# display.net
KiCad netlist of a schematic drawn in Altium Designer
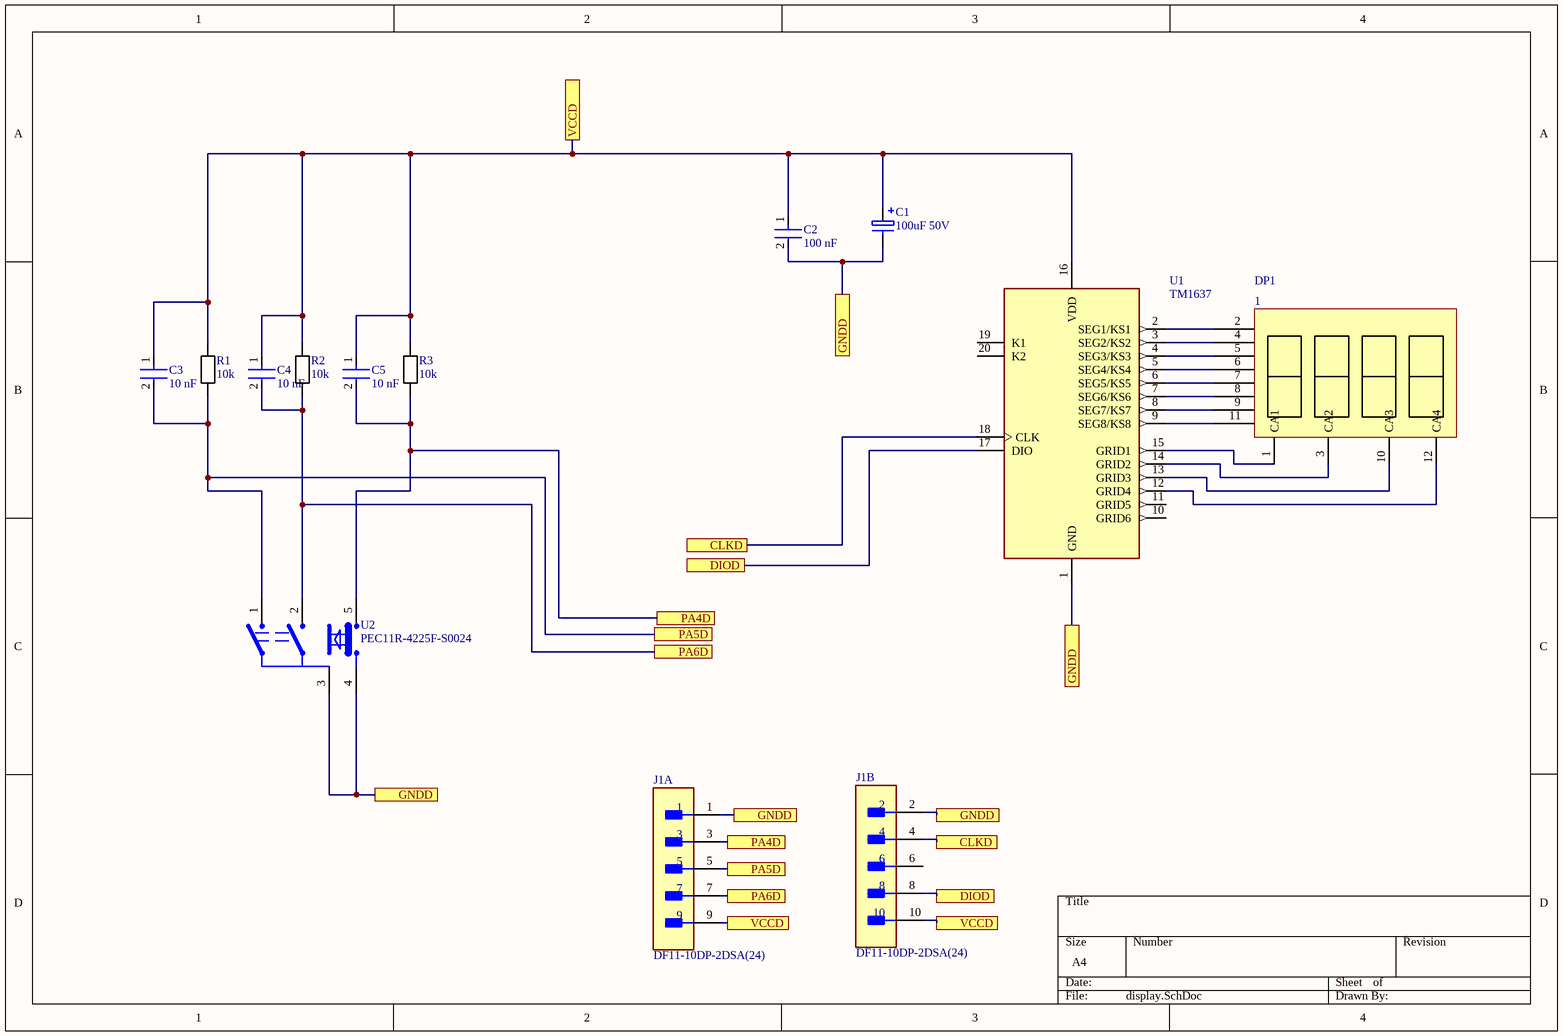
[diagram p0: display.SchDoc]

(export (version "E")
  (design (tool "Eeschema 10.0.6"))
  (components
    (comp (ref "1") (value "DP1") (footprint "7sigment") (libsource (lib "Schlib1") (part "7sigment")))
    (comp (ref "C1")
      (value "100uF 50V")
      (footprint "Elco 100uF 50V")
      (fields
        (field (name "PART NUMBER") "02015A270JAT2A")
        (field (name "MANUFACTURER") "AVX Interconnect / Elco")
      )
      (libsource (lib "Schlib1") (part "condensator 100uF 50V"))
    )
    (comp (ref "C2")
      (value "100 nF")
      (footprint "0805")
      (description "Chip Multilayer Ceramic Capacitors for General Purpose, 0805, 10uF, X5R, 15%, 10%, 25V")
      (fields (field (name "VOLTAGE") "25V") (field (name "TOLERANCE") "10%"))
      (libsource (lib "soldeerstation") (part "Condensator 0805"))
    )
    (comp (ref "C3")
      (value "10 nF")
      (footprint "0805")
      (description "Chip Multilayer Ceramic Capacitors for General Purpose, 0805, 10uF, X5R, 15%, 10%, 25V")
      (fields (field (name "VOLTAGE") "25V") (field (name "TOLERANCE") "10%"))
      (libsource (lib "soldeerstation") (part "Condensator 0805"))
    )
    (comp (ref "C4")
      (value "10 nF")
      (footprint "0805")
      (description "Chip Multilayer Ceramic Capacitors for General Purpose, 0805, 10uF, X5R, 15%, 10%, 25V")
      (fields (field (name "VOLTAGE") "25V") (field (name "TOLERANCE") "10%"))
      (libsource (lib "soldeerstation") (part "Condensator 0805"))
    )
    (comp (ref "C5")
      (value "10 nF")
      (footprint "0805")
      (description "Chip Multilayer Ceramic Capacitors for General Purpose, 0805, 10uF, X5R, 15%, 10%, 25V")
      (fields (field (name "VOLTAGE") "25V") (field (name "TOLERANCE") "10%"))
      (libsource (lib "soldeerstation") (part "Condensator 0805"))
    )
    (comp (ref "J1")
      (value "DF11-10DP-2DSA(24)")
      (footprint "FP-DF11-10DP-2DSA_24-MFG - duplicate")
      (description "CONN HEADER VERT 10POS 2MM")
      (fields
        (field (name "OCTOPART") "https://octopart.com/df11-10dp-2dsa%2824%29-hirose-39521433")
        (field (name "MANUFACTURER") "Hirose")
      )
      (libsource (lib "Schlib1") (part "CMP-11610-000008-1"))
    )
    (comp (ref "R1")
      (value "10k")
      (footprint "registor")
      (fields (field (name "MANUFACTURER") "Vishay Dale") (field (name "PART NUMBER") "CRCW08050000Z0EA"))
      (libsource (lib "Schlib1") (part "resistor"))
    )
    (comp (ref "R2")
      (value "10k")
      (footprint "registor")
      (fields (field (name "MANUFACTURER") "Vishay Dale") (field (name "PART NUMBER") "CRCW08050000Z0EA"))
      (libsource (lib "Schlib1") (part "resistor"))
    )
    (comp (ref "R3")
      (value "10k")
      (footprint "registor")
      (fields (field (name "MANUFACTURER") "Vishay Dale") (field (name "PART NUMBER") "CRCW08050000Z0EA"))
      (libsource (lib "Schlib1") (part "resistor"))
    )
    (comp (ref "U1")
      (value "TM1637")
      (footprint "TM1637")
      (description "LED Drive Control Special Circuit")
      (fields (field (name "MF") "Titan Micro Electronics"))
      (libsource (lib "soldeerstation") (part "TM1637"))
    )
    (comp (ref "U2")
      (value "PEC11R-4225F-S0024")
      (footprint "PEC12R-4XXXF-SXXXX_1")
      (description "Rotary Button")
      (fields (field (name "MOUSER PART NUMBER") "652-PEC11R-4225F-S24"))
      (libsource (lib "Schlib1") (part "encoder"))
    )
  )
  (nets
    (net (code "1") (name "/CLKD") (class "Default")
      (node (ref "J1") (pin "4") (pinfunction "4_4") (pintype "passive"))
      (node (ref "U1") (pin "18") (pinfunction "CLK_18") (pintype "passive"))
    )
    (net (code "2") (name "/DIOD") (class "Default")
      (node (ref "J1") (pin "8") (pinfunction "8_8") (pintype "passive"))
      (node (ref "U1") (pin "17") (pinfunction "DIO_17") (pintype "passive"))
    )
    (net (code "3") (name "/GNDD") (class "Default")
      (node (ref "C1") (pin "2") (pinfunction "2_2") (pintype "passive"))
      (node (ref "C2") (pin "2") (pinfunction "2_2") (pintype "passive"))
      (node (ref "J1") (pin "1") (pinfunction "1_1") (pintype "passive"))
      (node (ref "J1") (pin "2") (pinfunction "2_2") (pintype "passive"))
      (node (ref "U1") (pin "1") (pinfunction "GND_1") (pintype "power_in"))
      (node (ref "U2") (pin "3") (pinfunction "3_3") (pintype "passive"))
      (node (ref "U2") (pin "4") (pinfunction "4_4") (pintype "passive"))
    )
    (net (code "4") (name "/PA4D") (class "Default")
      (node (ref "C5") (pin "2") (pinfunction "2_2") (pintype "passive"))
      (node (ref "J1") (pin "3") (pinfunction "3_3") (pintype "passive"))
      (node (ref "R3") (pin "1") (pinfunction "1_1") (pintype "passive"))
      (node (ref "U2") (pin "5") (pinfunction "5_5") (pintype "passive"))
    )
    (net (code "5") (name "/PA5D") (class "Default")
      (node (ref "C3") (pin "2") (pinfunction "2_2") (pintype "passive"))
      (node (ref "J1") (pin "5") (pinfunction "5_5") (pintype "passive"))
      (node (ref "R1") (pin "1") (pinfunction "1_1") (pintype "passive"))
      (node (ref "U2") (pin "1") (pinfunction "1_1") (pintype "passive"))
    )
    (net (code "6") (name "/PA6D") (class "Default")
      (node (ref "C4") (pin "2") (pinfunction "2_2") (pintype "passive"))
      (node (ref "J1") (pin "7") (pinfunction "7_7") (pintype "passive"))
      (node (ref "R2") (pin "1") (pinfunction "1_1") (pintype "passive"))
      (node (ref "U2") (pin "2") (pinfunction "2_2") (pintype "passive"))
    )
    (net (code "7") (name "/VCCD") (class "Default")
      (node (ref "C1") (pin "1") (pinfunction "1_1") (pintype "passive"))
      (node (ref "C2") (pin "1") (pinfunction "1_1") (pintype "passive"))
      (node (ref "C3") (pin "1") (pinfunction "1_1") (pintype "passive"))
      (node (ref "C4") (pin "1") (pinfunction "1_1") (pintype "passive"))
      (node (ref "C5") (pin "1") (pinfunction "1_1") (pintype "passive"))
      (node (ref "J1") (pin "10") (pinfunction "10_10") (pintype "passive"))
      (node (ref "J1") (pin "9") (pinfunction "9_9") (pintype "passive"))
      (node (ref "R1") (pin "2") (pinfunction "2_2") (pintype "passive"))
      (node (ref "R2") (pin "2") (pinfunction "2_2") (pintype "passive"))
      (node (ref "R3") (pin "2") (pinfunction "2_2") (pintype "passive"))
      (node (ref "U1") (pin "16") (pinfunction "VDD_16") (pintype "power_in"))
    )
    (net (code "8") (name "Net-(1-CA1)") (class "Default")
      (node (ref "1") (pin "1") (pinfunction "CA1_1") (pintype "passive"))
      (node (ref "U1") (pin "15") (pinfunction "GRID1_15") (pintype "output"))
    )
    (net (code "9") (name "Net-(1-CA2)") (class "Default")
      (node (ref "1") (pin "3") (pinfunction "CA2_3") (pintype "passive"))
      (node (ref "U1") (pin "14") (pinfunction "GRID2_14") (pintype "output"))
    )
    (net (code "10") (name "Net-(1-CA3)") (class "Default")
      (node (ref "1") (pin "10") (pinfunction "CA3_10") (pintype "passive"))
      (node (ref "U1") (pin "13") (pinfunction "GRID3_13") (pintype "output"))
    )
    (net (code "11") (name "Net-(1-CA4)") (class "Default")
      (node (ref "1") (pin "12") (pinfunction "CA4_12") (pintype "passive"))
      (node (ref "U1") (pin "12") (pinfunction "GRID4_12") (pintype "output"))
    )
    (net (code "12") (name "Net-(U1-SEG1{slash}KS1)") (class "Default")
      (node (ref "1") (pin "2") (pintype "passive"))
      (node (ref "U1") (pin "2") (pinfunction "SEG1/KS1_2") (pintype "output"))
    )
    (net (code "13") (name "Net-(U1-SEG2{slash}KS2)") (class "Default")
      (node (ref "1") (pin "4") (pintype "passive"))
      (node (ref "U1") (pin "3") (pinfunction "SEG2/KS2_3") (pintype "output"))
    )
    (net (code "14") (name "Net-(U1-SEG3{slash}KS3)") (class "Default")
      (node (ref "1") (pin "5") (pintype "passive"))
      (node (ref "U1") (pin "4") (pinfunction "SEG3/KS3_4") (pintype "output"))
    )
    (net (code "15") (name "Net-(U1-SEG4{slash}KS4)") (class "Default")
      (node (ref "1") (pin "6") (pintype "passive"))
      (node (ref "U1") (pin "5") (pinfunction "SEG4/KS4_5") (pintype "output"))
    )
    (net (code "16") (name "Net-(U1-SEG5{slash}KS5)") (class "Default")
      (node (ref "1") (pin "7") (pintype "passive"))
      (node (ref "U1") (pin "6") (pinfunction "SEG5/KS5_6") (pintype "output"))
    )
    (net (code "17") (name "Net-(U1-SEG6{slash}KS6)") (class "Default")
      (node (ref "1") (pin "8") (pintype "passive"))
      (node (ref "U1") (pin "7") (pinfunction "SEG6/KS6_7") (pintype "output"))
    )
    (net (code "18") (name "Net-(U1-SEG7{slash}KS7)") (class "Default")
      (node (ref "1") (pin "9") (pintype "passive"))
      (node (ref "U1") (pin "8") (pinfunction "SEG7/KS7_8") (pintype "output"))
    )
    (net (code "19") (name "Net-(U1-SEG8{slash}KS8)") (class "Default")
      (node (ref "1") (pin "11") (pintype "passive"))
      (node (ref "U1") (pin "9") (pinfunction "SEG8/KS8_9") (pintype "output"))
    )
    (net (code "20") (name "unconnected-(J1-Pad6)") (class "Default")
      (node (ref "J1") (pin "6") (pinfunction "6_6") (pintype "passive"))
    )
    (net (code "21") (name "unconnected-(U1-GRID5-Pad11)") (class "Default")
      (node (ref "U1") (pin "11") (pinfunction "GRID5_11") (pintype "output"))
    )
    (net (code "22") (name "unconnected-(U1-GRID6-Pad10)") (class "Default")
      (node (ref "U1") (pin "10") (pinfunction "GRID6_10") (pintype "output"))
    )
    (net (code "23") (name "unconnected-(U1-K1-Pad19)") (class "Default")
      (node (ref "U1") (pin "19") (pinfunction "K1_19") (pintype "passive"))
    )
    (net (code "24") (name "unconnected-(U1-K2-Pad20)") (class "Default")
      (node (ref "U1") (pin "20") (pinfunction "K2_20") (pintype "passive"))
    )
  )
)
